# weblight_developer.net
KiCad netlist of a schematic drawn in EAGLE
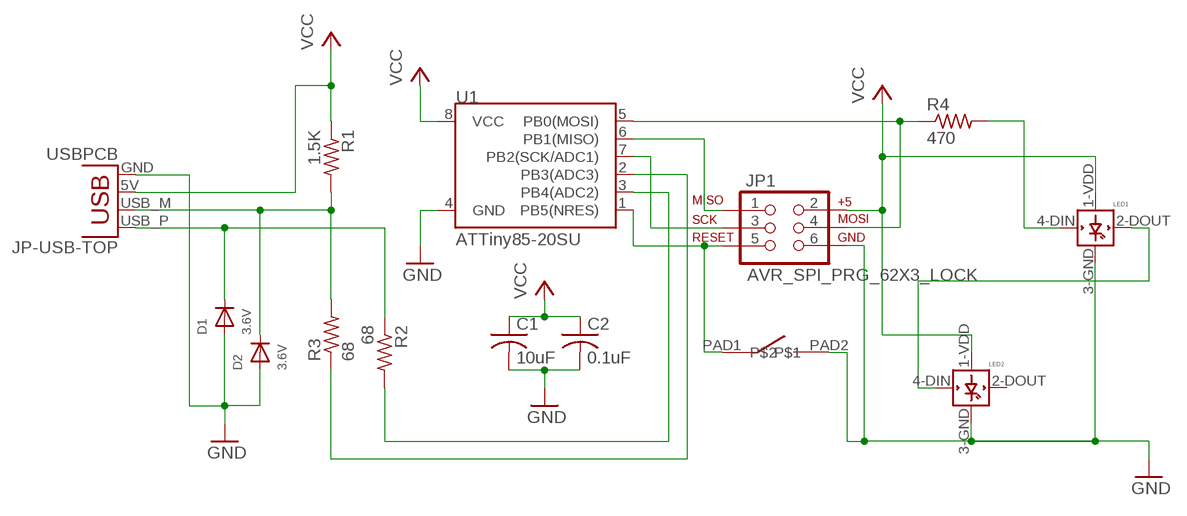
[diagram p0: schematic, sheet 1]

(export (version "E")
  (design (tool "Eeschema 10.0.6"))
  (components
    (comp (ref "C1")
      (value "10uF")
      (footprint "eagle-import:C0805")
      (libsource (lib "eagle-import") (part "C-USC0805"))
    )
    (comp (ref "C2")
      (value "0.1uF")
      (footprint "eagle-import:C0805")
      (libsource (lib "eagle-import") (part "C-USC0805"))
    )
    (comp (ref "D1")
      (value "3.6V")
      (footprint "eagle-import:SOD-323")
      (libsource (lib "eagle-import") (part "DIODESOD-323"))
    )
    (comp (ref "D2")
      (value "3.6V")
      (footprint "eagle-import:SOD-323")
      (libsource (lib "eagle-import") (part "DIODESOD-323"))
    )
    (comp (ref "JP-USB-TOP")
      (value "USBPCB")
      (footprint "eagle-import:USB-A-PCB")
      (libsource (lib "eagle-import") (part "USBPCB"))
    )
    (comp (ref "JP1")
      (value "AVR_SPI_PRG_62X3_LOCK")
      (footprint "eagle-import:2X3_LOCK")
      (libsource (lib "eagle-import") (part "AVR_SPI_PRG_62X3_LOCK"))
    )
    (comp (ref "LED1")
      (value "WS2812B")
      (footprint "eagle-import:WS2812B")
      (libsource (lib "eagle-import") (part "WS2812B"))
    )
    (comp (ref "LED2")
      (value "WS2812B")
      (footprint "eagle-import:WS2812B")
      (libsource (lib "eagle-import") (part "WS2812B"))
    )
    (comp (ref "R1")
      (value "1.5K")
      (footprint "eagle-import:R0805")
      (libsource (lib "eagle-import") (part "R-US_R0805"))
    )
    (comp (ref "R2")
      (value "68")
      (footprint "eagle-import:R0805")
      (libsource (lib "eagle-import") (part "R-US_R0805"))
    )
    (comp (ref "R3")
      (value "68")
      (footprint "eagle-import:R0805")
      (libsource (lib "eagle-import") (part "R-US_R0805"))
    )
    (comp (ref "R4")
      (value "470")
      (footprint "eagle-import:R0805")
      (libsource (lib "eagle-import") (part "R-US_R0805"))
    )
    (comp (ref "SW_RESET")
      (value "BUTTON_TD-85XU")
      (footprint "eagle-import:BUTTON_TD-85XU")
      (libsource (lib "eagle-import") (part "BUTTON_TD-85XU"))
    )
    (comp (ref "U1")
      (value "ATTiny85-20SU")
      (footprint "eagle-import:SO08-EIAJ")
      (libsource (lib "eagle-import") (part "ATTINY45TINY85-20-SMT"))
    )
  )
  (nets
    (net (code "1") (name "GND") (class "Default")
      (node (ref "C1") (pin "2") (pinfunction "2_2") (pintype "passive"))
      (node (ref "C2") (pin "2") (pinfunction "2_2") (pintype "passive"))
      (node (ref "D1") (pin "A") (pinfunction "A_A") (pintype "passive"))
      (node (ref "D2") (pin "A") (pinfunction "A_A") (pintype "passive"))
      (node (ref "JP-USB-TOP") (pin "GND") (pinfunction "GND_GND") (pintype "bidirectional"))
      (node (ref "JP1") (pin "6") (pinfunction "6_6") (pintype "passive"))
      (node (ref "LED1") (pin "3-GND") (pinfunction "GND_3-GND") (pintype "bidirectional"))
      (node (ref "LED2") (pin "3-GND") (pinfunction "GND_3-GND") (pintype "bidirectional"))
      (node (ref "SW_RESET") (pin "PAD2") (pinfunction "P$2_PAD2") (pintype "passive"))
      (node (ref "U1") (pin "4") (pinfunction "GND_4") (pintype "bidirectional"))
    )
    (net (code "2") (name "Net-(JP-USB-TOP-D+)") (class "Default")
      (node (ref "D1") (pin "C") (pinfunction "C_C") (pintype "passive"))
      (node (ref "JP-USB-TOP") (pin "USB_P") (pinfunction "D+_USB_P") (pintype "bidirectional"))
      (node (ref "R2") (pin "1") (pinfunction "1_1") (pintype "passive"))
    )
    (net (code "3") (name "Net-(JP-USB-TOP-D-)") (class "Default")
      (node (ref "D2") (pin "C") (pinfunction "C_C") (pintype "passive"))
      (node (ref "JP-USB-TOP") (pin "USB_M") (pinfunction "D-_USB_M") (pintype "bidirectional"))
      (node (ref "R1") (pin "2") (pinfunction "2_2") (pintype "passive"))
      (node (ref "R3") (pin "2") (pinfunction "2_2") (pintype "passive"))
    )
    (net (code "4") (name "Net-(LED1-DIN)") (class "Default")
      (node (ref "LED1") (pin "4-DIN") (pinfunction "DIN_4-DIN") (pintype "input"))
      (node (ref "R4") (pin "2") (pinfunction "2_2") (pintype "passive"))
    )
    (net (code "5") (name "Net-(LED1-DOUT)") (class "Default")
      (node (ref "LED1") (pin "2-DOUT") (pinfunction "DOUT_2-DOUT") (pintype "output"))
      (node (ref "LED2") (pin "4-DIN") (pinfunction "DIN_4-DIN") (pintype "input"))
    )
    (net (code "6") (name "Net-(SW_RESET-P$1)") (class "Default")
      (node (ref "JP1") (pin "5") (pinfunction "5_5") (pintype "passive"))
      (node (ref "SW_RESET") (pin "PAD1") (pinfunction "P$1_PAD1") (pintype "passive"))
      (node (ref "U1") (pin "1") (pinfunction "PB5(NRES)_1") (pintype "bidirectional"))
    )
    (net (code "7") (name "Net-(U1-PB0(MOSI))") (class "Default")
      (node (ref "JP1") (pin "4") (pinfunction "4_4") (pintype "passive"))
      (node (ref "R4") (pin "1") (pinfunction "1_1") (pintype "passive"))
      (node (ref "U1") (pin "5") (pinfunction "PB0(MOSI)_5") (pintype "bidirectional"))
    )
    (net (code "8") (name "Net-(U1-PB1(MISO))") (class "Default")
      (node (ref "JP1") (pin "1") (pinfunction "1_1") (pintype "passive"))
      (node (ref "U1") (pin "6") (pinfunction "PB1(MISO)_6") (pintype "bidirectional"))
    )
    (net (code "9") (name "Net-(U1-PB2(SCK{slash}ADC1))") (class "Default")
      (node (ref "JP1") (pin "3") (pinfunction "3_3") (pintype "passive"))
      (node (ref "U1") (pin "7") (pinfunction "PB2(SCK/ADC1)_7") (pintype "bidirectional"))
    )
    (net (code "10") (name "Net-(U1-PB3(ADC3))") (class "Default")
      (node (ref "R3") (pin "1") (pinfunction "1_1") (pintype "passive"))
      (node (ref "U1") (pin "2") (pinfunction "PB3(ADC3)_2") (pintype "bidirectional"))
    )
    (net (code "11") (name "Net-(U1-PB4(ADC2))") (class "Default")
      (node (ref "R2") (pin "2") (pinfunction "2_2") (pintype "passive"))
      (node (ref "U1") (pin "3") (pinfunction "PB4(ADC2)_3") (pintype "bidirectional"))
    )
    (net (code "12") (name "VCC") (class "Default")
      (node (ref "C1") (pin "1") (pinfunction "1_1") (pintype "passive"))
      (node (ref "C2") (pin "1") (pinfunction "1_1") (pintype "passive"))
      (node (ref "JP-USB-TOP") (pin "5V") (pinfunction "VBUS_5V") (pintype "bidirectional"))
      (node (ref "JP1") (pin "2") (pinfunction "2_2") (pintype "passive"))
      (node (ref "LED1") (pin "1-VDD") (pinfunction "VDD_1-VDD") (pintype "bidirectional"))
      (node (ref "LED2") (pin "1-VDD") (pinfunction "VDD_1-VDD") (pintype "bidirectional"))
      (node (ref "R1") (pin "1") (pinfunction "1_1") (pintype "passive"))
      (node (ref "U1") (pin "8") (pinfunction "VCC_8") (pintype "bidirectional"))
    )
    (net (code "13") (name "unconnected-(LED2-DOUT-Pad2-DOUT)") (class "Default")
      (node (ref "LED2") (pin "2-DOUT") (pinfunction "DOUT_2-DOUT") (pintype "output"))
    )
  )
)
